# Aquarium_LED_Driver.net
KiCad netlist of a schematic drawn in Altium Designer
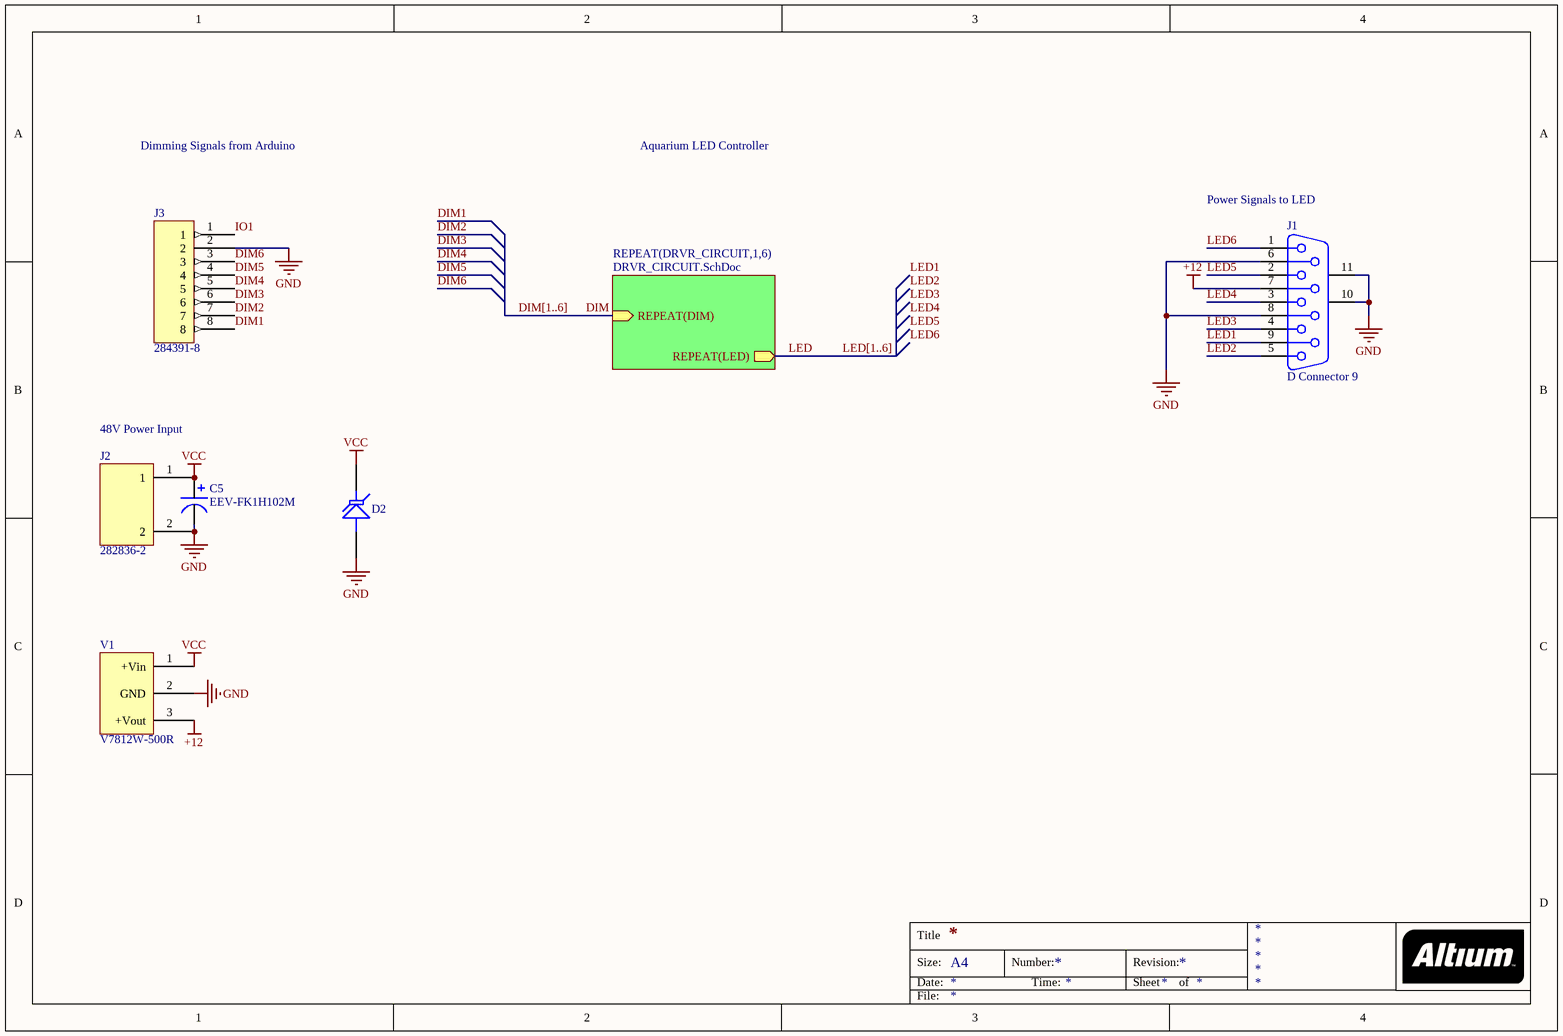
[diagram p0: Aquarium_LED_Driver.SchDoc]

(export (version "E")
  (design (tool "Eeschema 10.0.6"))
  (components
    (comp (ref "C5")
      (value "EEV-FK1H102M")
      (footprint "EEV-FK1H102M")
      (description "Aluminum Electrolytic Capcitor")
      (libsource (lib "Custom") (part "EEV-FK1H102M"))
    )
    (comp (ref "D2")
      (value "Tranzorb")
      (footprint "SMB")
      (description "Transient Voltage Suppression (TVS) Diode")
      (fields (field (name "PUBLISHER") "Altium Limited"))
      (libsource (lib "Miscellaneous Devices") (part "Tranzorb"))
    )
    (comp (ref "J1")
      (value "D Connector 9")
      (footprint "DSUB1.385-2H9")
      (description "Receptacle Assembly, 9 Position, Right Angle")
      (fields (field (name "PUBLISHER") "Altium Limited"))
      (libsource (lib "Miscellaneous Connectors") (part "D Connector 9"))
    )
    (comp (ref "J2")
      (value "282836-2")
      (footprint "282836-2")
      (description "Board Mount w/Interlock,  Low Profile,  5.0 mm Centerline,  Side Wire Entry")
      (libsource (lib "Custom") (part "282836-2"))
    )
    (comp (ref "J3")
      (value "284391-8")
      (footprint "284391-8")
      (description "8-Pos Eurostyle Terminal Block")
      (libsource (lib "Custom") (part "284391-8"))
    )
    (comp (ref "V1")
      (value "V7812W-500R")
      (footprint "V7812W-500R")
      (libsource (lib "Custom") (part "V7812W-500R"))
    )
  )
  (nets
    (net (code "1") (name "+12") (class "Default")
      (node (ref "J1") (pin "7") (pinfunction "7_7") (pintype "passive"))
      (node (ref "V1") (pin "3") (pinfunction "+Vout_3") (pintype "power_in"))
    )
    (net (code "3") (name "/DIM1") (class "Default")
      (node (ref "J3") (pin "8") (pinfunction "8_8") (pintype "output"))
    )
    (net (code "4") (name "/DIM2") (class "Default")
      (node (ref "J3") (pin "7") (pinfunction "7_7") (pintype "output"))
    )
    (net (code "5") (name "/DIM3") (class "Default")
      (node (ref "J3") (pin "6") (pinfunction "6_6") (pintype "output"))
    )
    (net (code "6") (name "/DIM4") (class "Default")
      (node (ref "J3") (pin "5") (pinfunction "5_5") (pintype "output"))
    )
    (net (code "7") (name "/DIM5") (class "Default")
      (node (ref "J3") (pin "4") (pinfunction "4_4") (pintype "output"))
    )
    (net (code "8") (name "/DIM6") (class "Default")
      (node (ref "J3") (pin "3") (pinfunction "3_3") (pintype "output"))
    )
    (net (code "10") (name "/IO1") (class "Default")
      (node (ref "J3") (pin "1") (pinfunction "1_1") (pintype "output"))
    )
    (net (code "12") (name "/LED1") (class "Default")
      (node (ref "J1") (pin "9") (pinfunction "9_9") (pintype "passive"))
    )
    (net (code "13") (name "/LED2") (class "Default")
      (node (ref "J1") (pin "5") (pinfunction "5_5") (pintype "passive"))
    )
    (net (code "14") (name "/LED3") (class "Default")
      (node (ref "J1") (pin "4") (pinfunction "4_4") (pintype "passive"))
    )
    (net (code "15") (name "/LED4") (class "Default")
      (node (ref "J1") (pin "3") (pinfunction "3_3") (pintype "passive"))
    )
    (net (code "16") (name "/LED5") (class "Default")
      (node (ref "J1") (pin "2") (pinfunction "2_2") (pintype "passive"))
    )
    (net (code "17") (name "/LED6") (class "Default")
      (node (ref "J1") (pin "1") (pinfunction "1_1") (pintype "passive"))
    )
    (net (code "19") (name "GND") (class "Default")
      (node (ref "C5") (pin "1") (pinfunction "-_1") (pintype "passive"))
      (node (ref "D2") (pin "1") (pinfunction "A_1") (pintype "passive"))
      (node (ref "J1") (pin "10") (pinfunction "MH1_10") (pintype "passive"))
      (node (ref "J1") (pin "11") (pinfunction "MH2_11") (pintype "passive"))
      (node (ref "J1") (pin "6") (pinfunction "6_6") (pintype "passive"))
      (node (ref "J1") (pin "8") (pinfunction "8_8") (pintype "passive"))
      (node (ref "J2") (pin "2") (pinfunction "2_2") (pintype "power_in"))
      (node (ref "J3") (pin "2") (pinfunction "2_2") (pintype "power_in"))
      (node (ref "V1") (pin "2") (pinfunction "GND_2") (pintype "power_in"))
    )
    (net (code "20") (name "VCC") (class "Default")
      (node (ref "C5") (pin "2") (pinfunction "+_2") (pintype "passive"))
      (node (ref "D2") (pin "2") (pinfunction "K_2") (pintype "passive"))
      (node (ref "J2") (pin "1") (pinfunction "1_1") (pintype "power_in"))
      (node (ref "V1") (pin "1") (pinfunction "+Vin_1") (pintype "power_in"))
    )
  )
)
